# TController.net
KiCad netlist of a schematic drawn in EAGLE
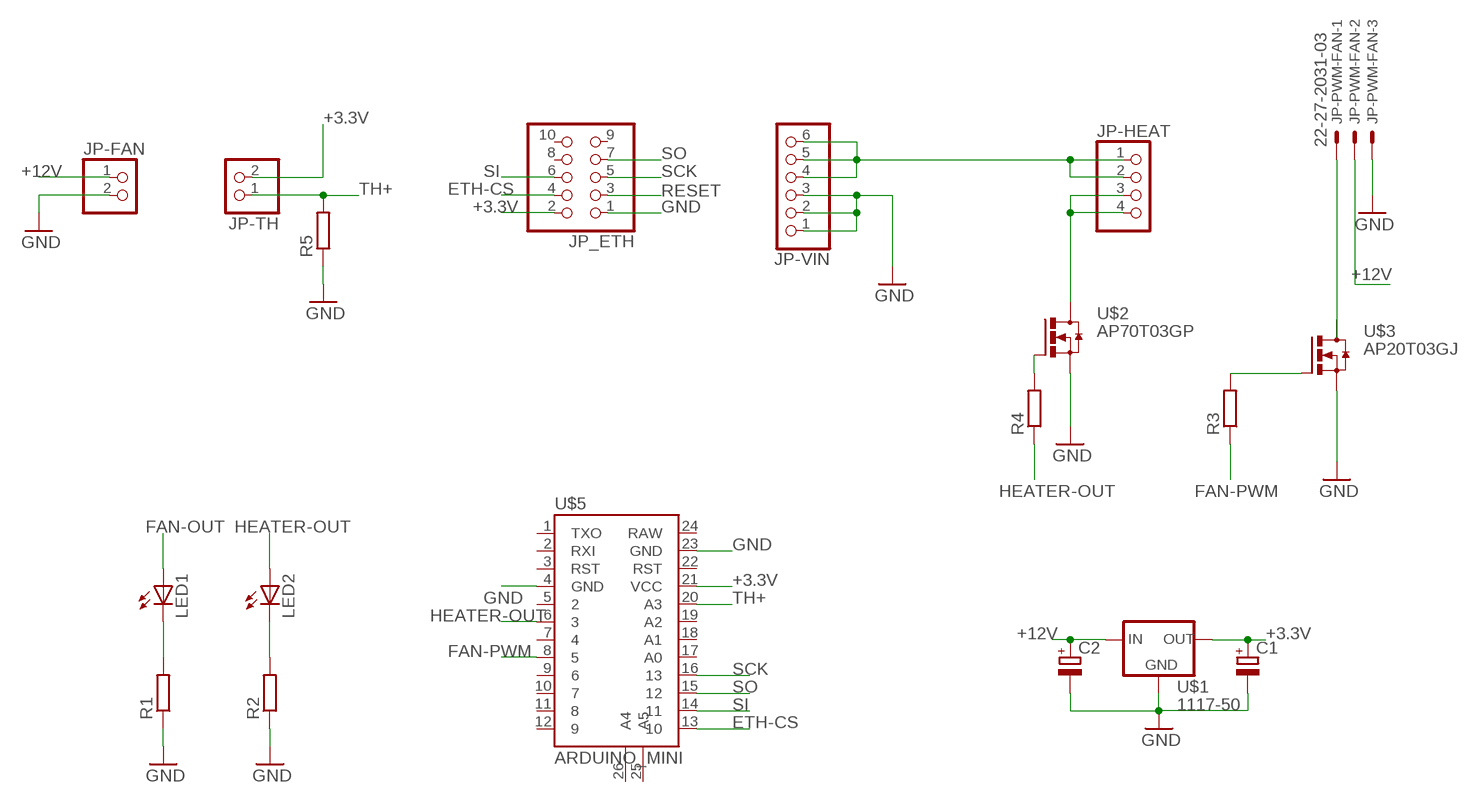
[diagram p0: schematic, sheet 1]

(export (version "E")
  (design (tool "Eeschema 10.0.6"))
  (components
    (comp (ref "C1")
      (value "CPOL-EUE2.5-6")
      (footprint "eagle-import:E2,5-6")
      (libsource (lib "eagle-import") (part "CPOL-EUE2.5-6"))
    )
    (comp (ref "C2")
      (value "CPOL-EUE2.5-6")
      (footprint "eagle-import:E2,5-6")
      (libsource (lib "eagle-import") (part "CPOL-EUE2.5-6"))
    )
    (comp (ref "JP-FAN")
      (value "PINHD-1X2")
      (footprint "eagle-import:1X02")
      (libsource (lib "eagle-import") (part "PINHD-1X2"))
    )
    (comp (ref "JP-HEAT")
      (value "PINHD-1X4")
      (footprint "eagle-import:1X04")
      (libsource (lib "eagle-import") (part "PINHD-1X4"))
    )
    (comp (ref "JP-PWM-FAN")
      (value "22-27-2031-03")
      (footprint "eagle-import:6410-03")
      (libsource (lib "eagle-import") (part "22-?-0327-2031"))
    )
    (comp (ref "JP-TH")
      (value "PINHD-1X2")
      (footprint "eagle-import:1X02")
      (libsource (lib "eagle-import") (part "PINHD-1X2"))
    )
    (comp (ref "JP-VIN")
      (value "PINHD-1X6")
      (footprint "eagle-import:1X06")
      (libsource (lib "eagle-import") (part "PINHD-1X6"))
    )
    (comp (ref "JP_ETH")
      (value "PINHD-2X5")
      (footprint "eagle-import:2X05")
      (libsource (lib "eagle-import") (part "PINHD-2X5"))
    )
    (comp (ref "LED1")
      (value "LED3MM")
      (footprint "eagle-import:LED3MM")
      (libsource (lib "eagle-import") (part "LED3MM"))
    )
    (comp (ref "LED2")
      (value "LED3MM")
      (footprint "eagle-import:LED3MM")
      (libsource (lib "eagle-import") (part "LED3MM"))
    )
    (comp (ref "R1")
      (value "R-EU_0207/10")
      (footprint "eagle-import:0207_10")
      (libsource (lib "eagle-import") (part "R-EU_0207/10"))
    )
    (comp (ref "R2")
      (value "R-EU_0207/10")
      (footprint "eagle-import:0207_10")
      (libsource (lib "eagle-import") (part "R-EU_0207/10"))
    )
    (comp (ref "R3")
      (value "R-EU_0207/10")
      (footprint "eagle-import:0207_10")
      (libsource (lib "eagle-import") (part "R-EU_0207/10"))
    )
    (comp (ref "R4")
      (value "R-EU_0207/10")
      (footprint "eagle-import:0207_10")
      (libsource (lib "eagle-import") (part "R-EU_0207/10"))
    )
    (comp (ref "R5")
      (value "R-EU_0207/10")
      (footprint "eagle-import:0207_10")
      (libsource (lib "eagle-import") (part "R-EU_0207/10"))
    )
    (comp (ref "U$1")
      (value "1117-50")
      (footprint "eagle-import:SOT223")
      (libsource (lib "eagle-import") (part "1117-50"))
    )
    (comp (ref "U$2")
      (value "AP70T03GP")
      (footprint "eagle-import:TO220V")
      (libsource (lib "eagle-import") (part "AP70T03GP"))
    )
    (comp (ref "U$3")
      (value "AP20T03GJ")
      (footprint "eagle-import:TO-251")
      (libsource (lib "eagle-import") (part "AP20T03GJ"))
    )
    (comp (ref "U$5")
      (value "ARDUINO_MINI")
      (footprint "eagle-import:ARDUINO_MINI")
      (libsource (lib "eagle-import") (part "ARDUINO_MINI"))
    )
  )
  (nets
    (net (code "1") (name "/+3.3V") (class "Default")
      (node (ref "C1") (pin "+") (pinfunction "+_+") (pintype "passive"))
      (node (ref "JP-TH") (pin "2") (pinfunction "2_2") (pintype "passive"))
      (node (ref "JP_ETH") (pin "2") (pinfunction "2_2") (pintype "passive"))
      (node (ref "U$1") (pin "2") (pinfunction "OUT_2") (pintype "passive"))
      (node (ref "U$1") (pin "4") (pinfunction "OUT_4") (pintype "passive"))
      (node (ref "U$5") (pin "21") (pinfunction "VCC_21") (pintype "bidirectional"))
    )
    (net (code "2") (name "/+12V") (class "Default")
      (node (ref "C2") (pin "+") (pinfunction "+_+") (pintype "passive"))
      (node (ref "JP-FAN") (pin "1") (pinfunction "1_1") (pintype "passive"))
      (node (ref "JP-HEAT") (pin "1") (pinfunction "1_1") (pintype "passive"))
      (node (ref "JP-HEAT") (pin "2") (pinfunction "2_2") (pintype "passive"))
      (node (ref "JP-PWM-FAN") (pin "2") (pinfunction "S_2") (pintype "passive"))
      (node (ref "JP-VIN") (pin "4") (pinfunction "4_4") (pintype "passive"))
      (node (ref "JP-VIN") (pin "5") (pinfunction "5_5") (pintype "passive"))
      (node (ref "JP-VIN") (pin "6") (pinfunction "6_6") (pintype "passive"))
      (node (ref "U$1") (pin "3") (pinfunction "IN_3") (pintype "input"))
    )
    (net (code "3") (name "/ETH-CS") (class "Default")
      (node (ref "JP_ETH") (pin "4") (pinfunction "4_4") (pintype "passive"))
      (node (ref "U$5") (pin "13") (pinfunction "10_13") (pintype "bidirectional"))
    )
    (net (code "4") (name "/FAN-OUT") (class "Default")
      (node (ref "LED1") (pin "A") (pinfunction "A_A") (pintype "passive"))
    )
    (net (code "5") (name "/FAN-PWM") (class "Default")
      (node (ref "R3") (pin "1") (pinfunction "1_1") (pintype "passive"))
      (node (ref "U$5") (pin "8") (pinfunction "5_8") (pintype "bidirectional"))
    )
    (net (code "6") (name "/HEATER-OUT") (class "Default")
      (node (ref "LED2") (pin "A") (pinfunction "A_A") (pintype "passive"))
      (node (ref "R4") (pin "1") (pinfunction "1_1") (pintype "passive"))
      (node (ref "U$5") (pin "6") (pinfunction "3_6") (pintype "bidirectional"))
    )
    (net (code "7") (name "/RESET") (class "Default")
      (node (ref "JP_ETH") (pin "3") (pinfunction "3_3") (pintype "passive"))
    )
    (net (code "8") (name "/SCK") (class "Default")
      (node (ref "JP_ETH") (pin "5") (pinfunction "5_5") (pintype "passive"))
      (node (ref "U$5") (pin "16") (pinfunction "13_16") (pintype "bidirectional"))
    )
    (net (code "9") (name "/SI") (class "Default")
      (node (ref "JP_ETH") (pin "6") (pinfunction "6_6") (pintype "passive"))
      (node (ref "U$5") (pin "14") (pinfunction "11_14") (pintype "bidirectional"))
    )
    (net (code "10") (name "/SO") (class "Default")
      (node (ref "JP_ETH") (pin "7") (pinfunction "7_7") (pintype "passive"))
      (node (ref "U$5") (pin "15") (pinfunction "12_15") (pintype "bidirectional"))
    )
    (net (code "11") (name "/TH+") (class "Default")
      (node (ref "JP-TH") (pin "1") (pinfunction "1_1") (pintype "passive"))
      (node (ref "R5") (pin "2") (pinfunction "2_2") (pintype "passive"))
      (node (ref "U$5") (pin "20") (pinfunction "A3_20") (pintype "bidirectional"))
    )
    (net (code "12") (name "GND") (class "Default")
      (node (ref "C1") (pin "-") (pinfunction "-_-") (pintype "passive"))
      (node (ref "C2") (pin "-") (pinfunction "-_-") (pintype "passive"))
      (node (ref "JP-FAN") (pin "2") (pinfunction "2_2") (pintype "passive"))
      (node (ref "JP-PWM-FAN") (pin "3") (pinfunction "S_3") (pintype "passive"))
      (node (ref "JP-VIN") (pin "1") (pinfunction "1_1") (pintype "passive"))
      (node (ref "JP-VIN") (pin "2") (pinfunction "2_2") (pintype "passive"))
      (node (ref "JP-VIN") (pin "3") (pinfunction "3_3") (pintype "passive"))
      (node (ref "JP_ETH") (pin "1") (pinfunction "1_1") (pintype "passive"))
      (node (ref "R1") (pin "1") (pinfunction "1_1") (pintype "passive"))
      (node (ref "R2") (pin "1") (pinfunction "1_1") (pintype "passive"))
      (node (ref "R5") (pin "1") (pinfunction "1_1") (pintype "passive"))
      (node (ref "U$1") (pin "1") (pinfunction "GND_1") (pintype "input"))
      (node (ref "U$2") (pin "3") (pinfunction "S_3") (pintype "passive"))
      (node (ref "U$3") (pin "S") (pinfunction "S_S") (pintype "passive"))
      (node (ref "U$5") (pin "23") (pinfunction "GND_23") (pintype "bidirectional"))
      (node (ref "U$5") (pin "4") (pinfunction "GND_4") (pintype "bidirectional"))
    )
    (net (code "13") (name "Net-(JP-PWM-FANA-S)") (class "Default")
      (node (ref "JP-PWM-FAN") (pin "1") (pinfunction "S_1") (pintype "passive"))
      (node (ref "U$3") (pin "D") (pinfunction "D_D") (pintype "passive"))
    )
    (net (code "14") (name "Net-(LED1-C)") (class "Default")
      (node (ref "LED1") (pin "K") (pinfunction "C_K") (pintype "passive"))
      (node (ref "R1") (pin "2") (pinfunction "2_2") (pintype "passive"))
    )
    (net (code "15") (name "Net-(LED2-C)") (class "Default")
      (node (ref "LED2") (pin "K") (pinfunction "C_K") (pintype "passive"))
      (node (ref "R2") (pin "2") (pinfunction "2_2") (pintype "passive"))
    )
    (net (code "16") (name "Net-(R3-Pad2)") (class "Default")
      (node (ref "R3") (pin "2") (pinfunction "2_2") (pintype "passive"))
      (node (ref "U$3") (pin "G") (pinfunction "G_G") (pintype "passive"))
    )
    (net (code "17") (name "Net-(U$2-D)") (class "Default")
      (node (ref "JP-HEAT") (pin "3") (pinfunction "3_3") (pintype "passive"))
      (node (ref "JP-HEAT") (pin "4") (pinfunction "4_4") (pintype "passive"))
      (node (ref "U$2") (pin "2") (pinfunction "D_2") (pintype "passive"))
    )
    (net (code "18") (name "Net-(U$2-G)") (class "Default")
      (node (ref "R4") (pin "2") (pinfunction "2_2") (pintype "passive"))
      (node (ref "U$2") (pin "1") (pinfunction "G_1") (pintype "passive"))
    )
    (net (code "19") (name "unconnected-(JP_ETH-Pad8)") (class "Default")
      (node (ref "JP_ETH") (pin "8") (pinfunction "8_8") (pintype "passive"))
    )
    (net (code "20") (name "unconnected-(JP_ETH-Pad9)") (class "Default")
      (node (ref "JP_ETH") (pin "9") (pinfunction "9_9") (pintype "passive"))
    )
    (net (code "21") (name "unconnected-(JP_ETH-Pad10)") (class "Default")
      (node (ref "JP_ETH") (pin "10") (pinfunction "10_10") (pintype "passive"))
    )
    (net (code "22") (name "unconnected-(U$5-2-Pad5)") (class "Default")
      (node (ref "U$5") (pin "5") (pinfunction "2_5") (pintype "bidirectional"))
    )
    (net (code "23") (name "unconnected-(U$5-4-Pad7)") (class "Default")
      (node (ref "U$5") (pin "7") (pinfunction "4_7") (pintype "bidirectional"))
    )
    (net (code "24") (name "unconnected-(U$5-6-Pad9)") (class "Default")
      (node (ref "U$5") (pin "9") (pinfunction "6_9") (pintype "bidirectional"))
    )
    (net (code "25") (name "unconnected-(U$5-7-Pad10)") (class "Default")
      (node (ref "U$5") (pin "10") (pinfunction "7_10") (pintype "bidirectional"))
    )
    (net (code "26") (name "unconnected-(U$5-8-Pad11)") (class "Default")
      (node (ref "U$5") (pin "11") (pinfunction "8_11") (pintype "bidirectional"))
    )
    (net (code "27") (name "unconnected-(U$5-9-Pad12)") (class "Default")
      (node (ref "U$5") (pin "12") (pinfunction "9_12") (pintype "bidirectional"))
    )
    (net (code "28") (name "unconnected-(U$5-A0-Pad17)") (class "Default")
      (node (ref "U$5") (pin "17") (pinfunction "A0_17") (pintype "bidirectional"))
    )
    (net (code "29") (name "unconnected-(U$5-A1-Pad18)") (class "Default")
      (node (ref "U$5") (pin "18") (pinfunction "A1_18") (pintype "bidirectional"))
    )
    (net (code "30") (name "unconnected-(U$5-A2-Pad19)") (class "Default")
      (node (ref "U$5") (pin "19") (pinfunction "A2_19") (pintype "bidirectional"))
    )
    (net (code "31") (name "unconnected-(U$5-A4-Pad26)") (class "Default")
      (node (ref "U$5") (pin "26") (pinfunction "A4_26") (pintype "bidirectional"))
    )
    (net (code "32") (name "unconnected-(U$5-A5-Pad25)") (class "Default")
      (node (ref "U$5") (pin "25") (pinfunction "A5_25") (pintype "bidirectional"))
    )
    (net (code "33") (name "unconnected-(U$5-RAW-Pad24)") (class "Default")
      (node (ref "U$5") (pin "24") (pinfunction "RAW_24") (pintype "bidirectional"))
    )
    (net (code "34") (name "unconnected-(U$5-RST-Pad3)") (class "Default")
      (node (ref "U$5") (pin "3") (pinfunction "RST_3") (pintype "bidirectional"))
    )
    (net (code "35") (name "unconnected-(U$5-RST-Pad22)") (class "Default")
      (node (ref "U$5") (pin "22") (pinfunction "RST_22") (pintype "bidirectional"))
    )
    (net (code "36") (name "unconnected-(U$5-RXI-Pad2)") (class "Default")
      (node (ref "U$5") (pin "2") (pinfunction "RXI_2") (pintype "bidirectional"))
    )
    (net (code "37") (name "unconnected-(U$5-TXO-Pad1)") (class "Default")
      (node (ref "U$5") (pin "1") (pinfunction "TXO_1") (pintype "bidirectional"))
    )
  )
)
